# fonte.net
KiCad netlist of a schematic drawn in EAGLE
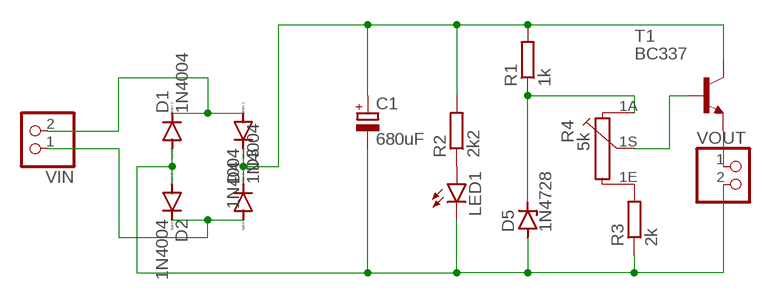
[diagram p0: schematic, sheet 1]

(export (version "E")
  (design (tool "Eeschema 10.0.6"))
  (components
    (comp (ref "C1")
      (value "680uF")
      (footprint "eagle-import:E5-10,5")
      (libsource (lib "eagle-import") (part "CPOL-EUE5-10.5"))
    )
    (comp (ref "D1")
      (value "1N4004")
      (footprint "eagle-import:DO41-10")
      (libsource (lib "eagle-import") (part "1N4004"))
    )
    (comp (ref "D2")
      (value "1N4004")
      (footprint "eagle-import:DO41-10")
      (libsource (lib "eagle-import") (part "1N4004"))
    )
    (comp (ref "D3")
      (value "1N4004")
      (footprint "eagle-import:DO41-10")
      (libsource (lib "eagle-import") (part "1N4004"))
    )
    (comp (ref "D4")
      (value "1N4004")
      (footprint "eagle-import:DO41-10")
      (libsource (lib "eagle-import") (part "1N4004"))
    )
    (comp (ref "D5")
      (value "1N4728")
      (footprint "eagle-import:DO41Z10")
      (libsource (lib "eagle-import") (part "1N4728"))
    )
    (comp (ref "LED1")
      (value "LED5MM")
      (footprint "eagle-import:LED5MM")
      (libsource (lib "eagle-import") (part "LED5MM"))
    )
    (comp (ref "R1")
      (value "1k")
      (footprint "eagle-import:0207_10")
      (libsource (lib "eagle-import") (part "R-EU_0207/10"))
    )
    (comp (ref "R2")
      (value "2k2")
      (footprint "eagle-import:0207_10")
      (libsource (lib "eagle-import") (part "R-EU_0207/10"))
    )
    (comp (ref "R3")
      (value "2k")
      (footprint "eagle-import:0207_10")
      (libsource (lib "eagle-import") (part "R-EU_0207/10"))
    )
    (comp (ref "R4")
      (value "5k")
      (footprint "eagle-import:PC16S")
      (libsource (lib "eagle-import") (part "PC16S"))
    )
    (comp (ref "T1")
      (value "BC337")
      (footprint "eagle-import:TO92")
      (libsource (lib "eagle-import") (part "BC337"))
    )
    (comp (ref "VIN")
      (value "PINHD-1X2")
      (footprint "eagle-import:1X02")
      (libsource (lib "eagle-import") (part "PINHD-1X2"))
    )
    (comp (ref "VOUT")
      (value "PINHD-1X2")
      (footprint "eagle-import:1X02")
      (libsource (lib "eagle-import") (part "PINHD-1X2"))
    )
  )
  (nets
    (net (code "1") (name "Net-(D1-PadC)") (class "Default")
      (node (ref "D1") (pin "C") (pinfunction "C_C") (pintype "passive"))
      (node (ref "D3") (pin "A") (pinfunction "A_A") (pintype "passive"))
      (node (ref "VIN") (pin "2") (pinfunction "2_2") (pintype "passive"))
    )
    (net (code "2") (name "Net-(D2-PadC)") (class "Default")
      (node (ref "D2") (pin "C") (pinfunction "C_C") (pintype "passive"))
      (node (ref "D4") (pin "A") (pinfunction "A_A") (pintype "passive"))
      (node (ref "VIN") (pin "1") (pinfunction "1_1") (pintype "passive"))
    )
    (net (code "3") (name "Net-(D5-PadC)") (class "Default")
      (node (ref "D5") (pin "C") (pinfunction "C_C") (pintype "passive"))
      (node (ref "R1") (pin "1") (pinfunction "1_1") (pintype "passive"))
      (node (ref "R4") (pin "1A") (pinfunction "1A_1A") (pintype "passive"))
    )
    (net (code "4") (name "Net-(LED1-C)") (class "Default")
      (node (ref "C1") (pin "-") (pinfunction "-_-") (pintype "passive"))
      (node (ref "D1") (pin "A") (pinfunction "A_A") (pintype "passive"))
      (node (ref "D2") (pin "A") (pinfunction "A_A") (pintype "passive"))
      (node (ref "D5") (pin "A") (pinfunction "A_A") (pintype "passive"))
      (node (ref "LED1") (pin "K") (pinfunction "C_K") (pintype "passive"))
      (node (ref "R3") (pin "1") (pinfunction "1_1") (pintype "passive"))
      (node (ref "VOUT") (pin "2") (pinfunction "2_2") (pintype "passive"))
    )
    (net (code "5") (name "Net-(LED1-PadA)") (class "Default")
      (node (ref "LED1") (pin "A") (pinfunction "A_A") (pintype "passive"))
      (node (ref "R2") (pin "1") (pinfunction "1_1") (pintype "passive"))
    )
    (net (code "6") (name "Net-(R3-Pad2)") (class "Default")
      (node (ref "R3") (pin "2") (pinfunction "2_2") (pintype "passive"))
      (node (ref "R4") (pin "1E") (pinfunction "1E_1E") (pintype "passive"))
    )
    (net (code "7") (name "Net-(T1-B)") (class "Default")
      (node (ref "R4") (pin "1S") (pinfunction "1S_1S") (pintype "passive"))
      (node (ref "T1") (pin "2") (pinfunction "B_2") (pintype "passive"))
    )
    (net (code "8") (name "Net-(T1-C)") (class "Default")
      (node (ref "C1") (pin "+") (pinfunction "+_+") (pintype "passive"))
      (node (ref "D3") (pin "C") (pinfunction "C_C") (pintype "passive"))
      (node (ref "D4") (pin "C") (pinfunction "C_C") (pintype "passive"))
      (node (ref "R1") (pin "2") (pinfunction "2_2") (pintype "passive"))
      (node (ref "R2") (pin "2") (pinfunction "2_2") (pintype "passive"))
      (node (ref "T1") (pin "3") (pinfunction "C_3") (pintype "passive"))
    )
    (net (code "9") (name "Net-(T1-E)") (class "Default")
      (node (ref "T1") (pin "1") (pinfunction "E_1") (pintype "passive"))
      (node (ref "VOUT") (pin "1") (pinfunction "1_1") (pintype "passive"))
    )
  )
)
